# osi-blank.net
KiCad netlist of a schematic drawn in EAGLE
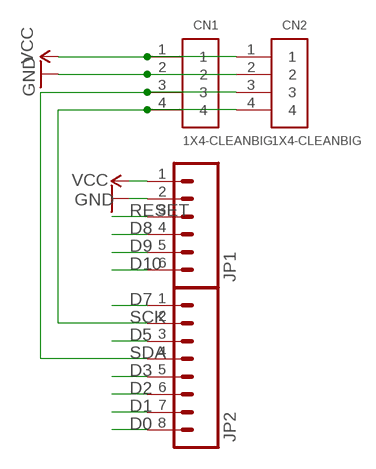
[diagram p0: schematic, sheet 1]

(export (version "E")
  (design (tool "Eeschema 10.0.6"))
  (components
    (comp (ref "CN1")
      (value "1X4-CLEANBIG")
      (footprint "eagle-import:1X04-CLEANBIG")
      (libsource (lib "eagle-import") (part "1X4-CLEANBIG"))
    )
    (comp (ref "CN2")
      (value "1X4-CLEANBIG")
      (footprint "eagle-import:1X04-CLEANBIG")
      (libsource (lib "eagle-import") (part "1X4-CLEANBIG"))
    )
    (comp (ref "JP1")
      (value "M06SIP")
      (footprint "eagle-import:1X06")
      (libsource (lib "eagle-import") (part "M06SIP"))
    )
    (comp (ref "JP2")
      (value "M081X08")
      (footprint "eagle-import:1X08")
      (libsource (lib "eagle-import") (part "M081X08"))
    )
  )
  (nets
    (net (code "1") (name "/D0") (class "Default")
      (node (ref "JP2") (pin "8") (pinfunction "8_8") (pintype "passive"))
    )
    (net (code "2") (name "/D1") (class "Default")
      (node (ref "JP2") (pin "7") (pinfunction "7_7") (pintype "passive"))
    )
    (net (code "3") (name "/D2") (class "Default")
      (node (ref "JP2") (pin "6") (pinfunction "6_6") (pintype "passive"))
    )
    (net (code "4") (name "/D3") (class "Default")
      (node (ref "JP2") (pin "5") (pinfunction "5_5") (pintype "passive"))
    )
    (net (code "5") (name "/D5") (class "Default")
      (node (ref "JP2") (pin "3") (pinfunction "3_3") (pintype "passive"))
    )
    (net (code "6") (name "/D7") (class "Default")
      (node (ref "JP2") (pin "1") (pinfunction "1_1") (pintype "passive"))
    )
    (net (code "7") (name "/D8") (class "Default")
      (node (ref "JP1") (pin "4") (pinfunction "4_4") (pintype "passive"))
    )
    (net (code "8") (name "/D9") (class "Default")
      (node (ref "JP1") (pin "5") (pinfunction "5_5") (pintype "passive"))
    )
    (net (code "9") (name "/D10") (class "Default")
      (node (ref "JP1") (pin "6") (pinfunction "6_6") (pintype "passive"))
    )
    (net (code "10") (name "/RESET") (class "Default")
      (node (ref "JP1") (pin "3") (pinfunction "3_3") (pintype "passive"))
    )
    (net (code "11") (name "/SCK") (class "Default")
      (node (ref "CN1") (pin "4") (pinfunction "4_4") (pintype "bidirectional"))
      (node (ref "CN2") (pin "4") (pinfunction "4_4") (pintype "bidirectional"))
      (node (ref "JP2") (pin "2") (pinfunction "2_2") (pintype "passive"))
    )
    (net (code "12") (name "/SDA") (class "Default")
      (node (ref "CN1") (pin "3") (pinfunction "3_3") (pintype "bidirectional"))
      (node (ref "CN2") (pin "3") (pinfunction "3_3") (pintype "bidirectional"))
      (node (ref "JP2") (pin "4") (pinfunction "4_4") (pintype "passive"))
    )
    (net (code "13") (name "GND") (class "Default")
      (node (ref "CN1") (pin "2") (pinfunction "2_2") (pintype "bidirectional"))
      (node (ref "CN2") (pin "2") (pinfunction "2_2") (pintype "bidirectional"))
      (node (ref "JP1") (pin "2") (pinfunction "2_2") (pintype "passive"))
    )
    (net (code "14") (name "VCC") (class "Default")
      (node (ref "CN1") (pin "1") (pinfunction "1_1") (pintype "bidirectional"))
      (node (ref "CN2") (pin "1") (pinfunction "1_1") (pintype "bidirectional"))
      (node (ref "JP1") (pin "1") (pinfunction "1_1") (pintype "passive"))
    )
  )
)
